# plantSensor.net
KiCad netlist of a schematic drawn in EAGLE
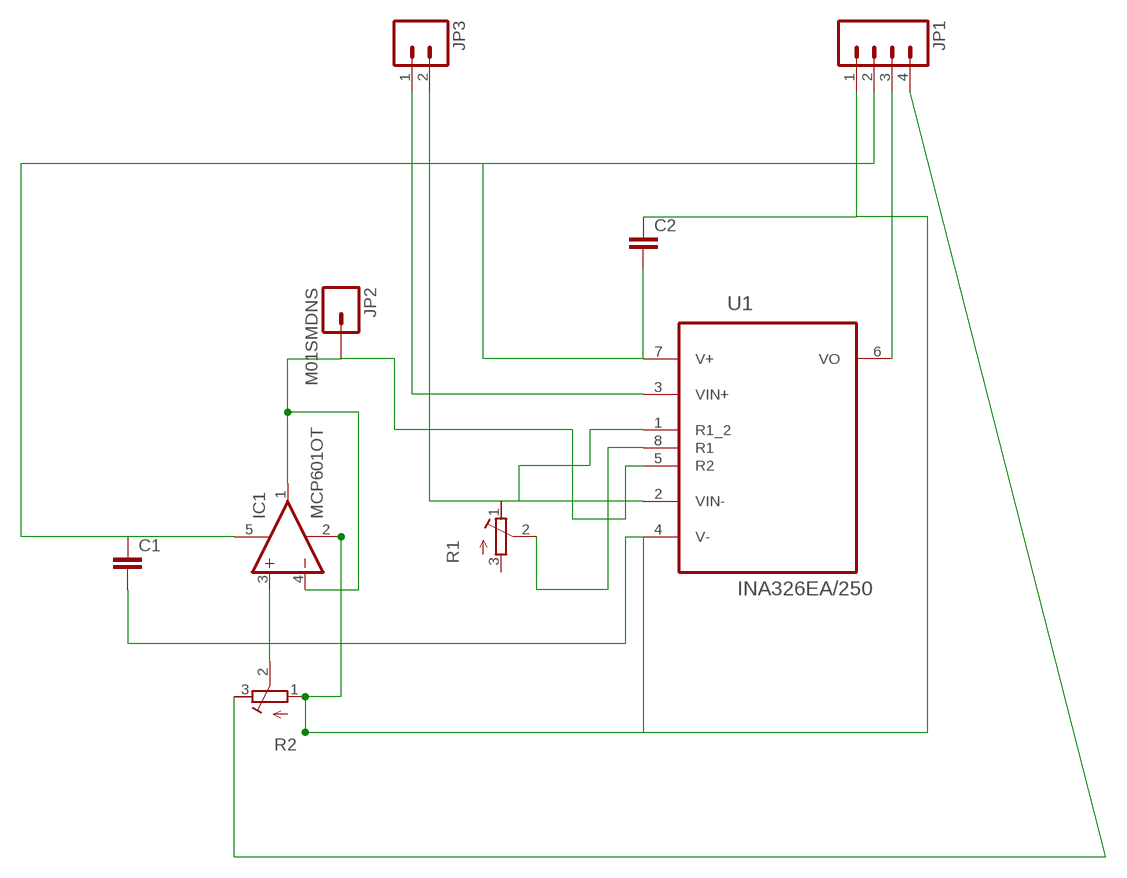
[diagram p0: schematic, sheet 1]

(export (version "E")
  (design (tool "Eeschema 10.0.6"))
  (components
    (comp (ref "C1")
      (value "C2.5/4")
      (footprint "eagle-import:C2.5-4")
      (libsource (lib "eagle-import") (part "C2.5/4"))
    )
    (comp (ref "C2")
      (value "C2.5/4")
      (footprint "eagle-import:C2.5-4")
      (libsource (lib "eagle-import") (part "C2.5/4"))
    )
    (comp (ref "IC1")
      (value "MCP601OT")
      (footprint "eagle-import:SOT23-5")
      (libsource (lib "eagle-import") (part "MCP601OT"))
    )
    (comp (ref "JP1")
      (value "M04PTH")
      (footprint "eagle-import:1X04")
      (libsource (lib "eagle-import") (part "M04PTH"))
    )
    (comp (ref "JP2")
      (value "M01SMDNS")
      (footprint "eagle-import:1X01NS")
      (libsource (lib "eagle-import") (part "M01SMDNS"))
    )
    (comp (ref "JP3")
      (value "M02PTH")
      (footprint "eagle-import:1X02")
      (libsource (lib "eagle-import") (part "M02PTH"))
    )
    (comp (ref "R1")
      (value "R-TRIMM3314G")
      (footprint "eagle-import:RTRIM3314G")
      (libsource (lib "eagle-import") (part "R-TRIMM3314G"))
    )
    (comp (ref "R2")
      (value "R-TRIMM3314J")
      (footprint "eagle-import:RTRIM3314J")
      (libsource (lib "eagle-import") (part "resistor_R-TRIMM3314J"))
    )
    (comp (ref "U1")
      (value "INA326EA/250")
      (footprint "eagle-import:SOP65P490X110-8N")
      (libsource (lib "eagle-import") (part "INA326EA/250"))
    )
  )
  (nets
    (net (code "1") (name "Net-(IC1-+IN)") (class "Default")
      (node (ref "IC1") (pin "3") (pinfunction "+IN_3") (pintype "input"))
      (node (ref "R2") (pin "2") (pinfunction "S_2") (pintype "passive"))
    )
    (net (code "2") (name "Net-(IC1--IN)") (class "Default")
      (node (ref "IC1") (pin "1") (pinfunction "OUT_1") (pintype "output"))
      (node (ref "IC1") (pin "4") (pinfunction "-IN_4") (pintype "input"))
      (node (ref "JP2") (pin "1") (pinfunction "1_1") (pintype "passive"))
      (node (ref "U1") (pin "5") (pinfunction "R2_5") (pintype "input"))
    )
    (net (code "3") (name "Net-(IC1-V+)") (class "Default")
      (node (ref "C1") (pin "1") (pinfunction "1_1") (pintype "passive"))
      (node (ref "C2") (pin "2") (pinfunction "2_2") (pintype "passive"))
      (node (ref "IC1") (pin "5") (pinfunction "V+_5") (pintype "power_in"))
      (node (ref "JP1") (pin "2") (pinfunction "2_2") (pintype "passive"))
      (node (ref "U1") (pin "7") (pinfunction "V+_7") (pintype "power_in"))
    )
    (net (code "4") (name "Net-(IC1-V-)") (class "Default")
      (node (ref "C1") (pin "2") (pinfunction "2_2") (pintype "passive"))
      (node (ref "C2") (pin "1") (pinfunction "1_1") (pintype "passive"))
      (node (ref "IC1") (pin "2") (pinfunction "V-_2") (pintype "power_in"))
      (node (ref "JP1") (pin "1") (pinfunction "1_1") (pintype "passive"))
      (node (ref "R2") (pin "1") (pinfunction "E_1") (pintype "passive"))
      (node (ref "U1") (pin "4") (pinfunction "V-_4") (pintype "power_in"))
    )
    (net (code "5") (name "Net-(R1-E)") (class "Default")
      (node (ref "R1") (pin "1") (pinfunction "E_1") (pintype "passive"))
      (node (ref "U1") (pin "1") (pinfunction "R1_2_1") (pintype "input"))
    )
    (net (code "6") (name "Net-(R1-S)") (class "Default")
      (node (ref "R1") (pin "2") (pinfunction "S_2") (pintype "passive"))
      (node (ref "U1") (pin "8") (pinfunction "R1_8") (pintype "input"))
    )
    (net (code "7") (name "Net-(R2-A)") (class "Default")
      (node (ref "JP1") (pin "4") (pinfunction "4_4") (pintype "passive"))
      (node (ref "R2") (pin "3") (pinfunction "A_3") (pintype "passive"))
    )
    (net (code "8") (name "Net-(U1-VIN+)") (class "Default")
      (node (ref "JP3") (pin "1") (pinfunction "1_1") (pintype "passive"))
      (node (ref "U1") (pin "3") (pinfunction "VIN+_3") (pintype "input"))
    )
    (net (code "9") (name "Net-(U1-VIN-)") (class "Default")
      (node (ref "JP3") (pin "2") (pinfunction "2_2") (pintype "passive"))
      (node (ref "U1") (pin "2") (pinfunction "VIN-_2") (pintype "input"))
    )
    (net (code "10") (name "Net-(U1-VO)") (class "Default")
      (node (ref "JP1") (pin "3") (pinfunction "3_3") (pintype "passive"))
      (node (ref "U1") (pin "6") (pinfunction "VO_6") (pintype "output"))
    )
    (net (code "11") (name "unconnected-(R1-A-Pad3)") (class "Default")
      (node (ref "R1") (pin "3") (pinfunction "A_3") (pintype "passive"))
    )
  )
)
